# emonTH_V1_4.net
KiCad netlist of a schematic drawn in EAGLE
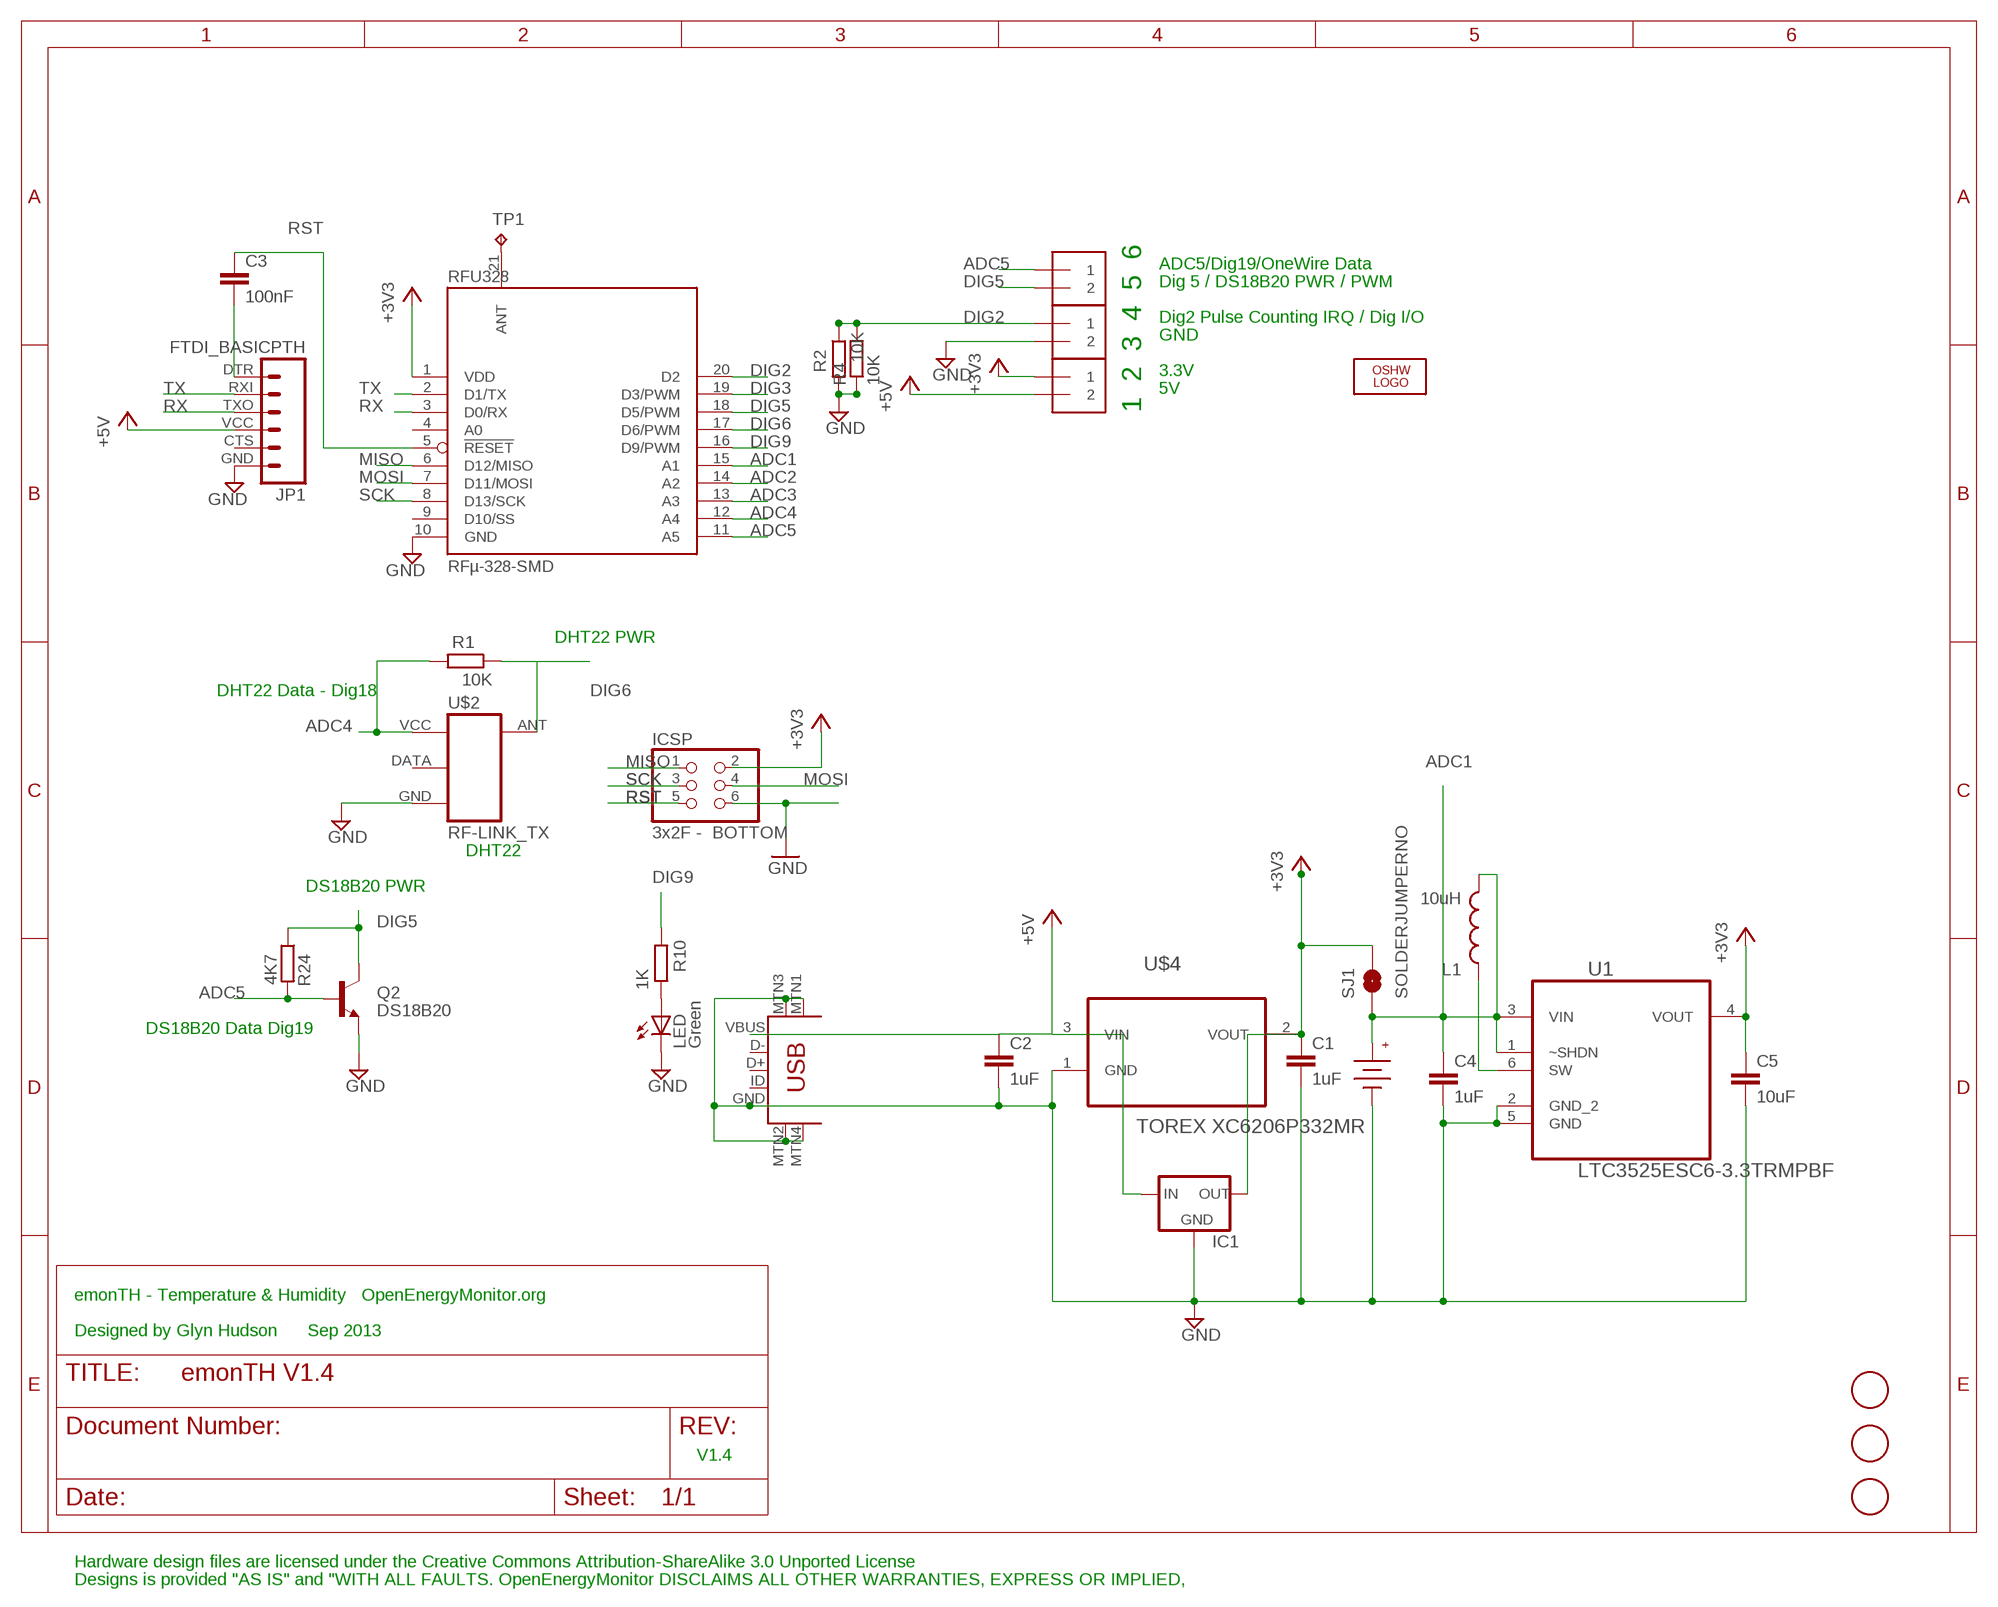
[diagram p0: schematic, sheet 1]

(export (version "E")
  (design (tool "Eeschema 10.0.6"))
  (components
    (comp (ref "C1")
      (value "1uF")
      (footprint "eagle-import:C0603")
      (libsource (lib "eagle-import") (part "C-EUC0603"))
    )
    (comp (ref "C2")
      (value "1uF")
      (footprint "eagle-import:C0603")
      (libsource (lib "eagle-import") (part "C-EUC0603"))
    )
    (comp (ref "C3")
      (value "100nF")
      (footprint "eagle-import:C0603")
      (libsource (lib "eagle-import") (part "C-EUC0603"))
    )
    (comp (ref "C4")
      (value "1uF")
      (footprint "eagle-import:C0603")
      (libsource (lib "eagle-import") (part "C-EUC0603"))
    )
    (comp (ref "C5")
      (value "10uF")
      (footprint "eagle-import:C0603")
      (libsource (lib "eagle-import") (part "C-EUC0603"))
    )
    (comp (ref "IC1")
      (value "78XXS")
      (footprint "eagle-import:78XXS")
      (libsource (lib "eagle-import") (part "78XXS"))
    )
    (comp (ref "ICSP")
      (value "3x2F - BOTTOM")
      (footprint "eagle-import:2X03")
      (libsource (lib "eagle-import") (part "PINHD-2X3"))
    )
    (comp (ref "J1")
      (value "1X2-3.5MM")
      (footprint "eagle-import:1X2-3.5MM")
      (libsource (lib "eagle-import") (part "1X2-3.5MM"))
    )
    (comp (ref "J2")
      (value "1X2-3.5MM")
      (footprint "eagle-import:1X2-3.5MM")
      (libsource (lib "eagle-import") (part "1X2-3.5MM"))
    )
    (comp (ref "J3")
      (value "1X2-3.5MM")
      (footprint "eagle-import:1X2-3.5MM")
      (libsource (lib "eagle-import") (part "1X2-3.5MM"))
    )
    (comp (ref "JP1")
      (value "FTDI_BASICPTH")
      (footprint "eagle-import:FTDI_BASIC")
      (libsource (lib "eagle-import") (part "FTDI_BASICPTH"))
    )
    (comp (ref "L1")
      (value "10uH")
      (footprint "eagle-import:1210")
      (libsource (lib "eagle-import") (part "INDUCTOR1210"))
    )
    (comp (ref "LED")
      (value "Green")
      (footprint "eagle-import:CHIP-LED0805")
      (libsource (lib "eagle-import") (part "LEDCHIP-LED0805"))
    )
    (comp (ref "LOGO1")
      (value "OSHW_LOGO_10MILX0200-NT")
      (footprint "eagle-import:OSHW_10X200_NOTEXT")
      (libsource (lib "eagle-import") (part "OSHW_LOGO_10MILX0200-NT"))
    )
    (comp (ref "Q2")
      (value "DS18B20")
      (footprint "eagle-import:TO-92")
      (libsource (lib "eagle-import") (part "TRANSISTOR_NPNTO92"))
    )
    (comp (ref "R1")
      (value "10K")
      (footprint "eagle-import:R0603")
      (libsource (lib "eagle-import") (part "resistor_R-EU_R0603"))
    )
    (comp (ref "R2")
      (value "10K")
      (footprint "eagle-import:R0603")
      (libsource (lib "eagle-import") (part "resistor_R-EU_R0603"))
    )
    (comp (ref "R4")
      (value "10K")
      (footprint "eagle-import:0204_7")
      (libsource (lib "eagle-import") (part "R-EU_0204/7"))
    )
    (comp (ref "R10")
      (value "1K")
      (footprint "eagle-import:R0603")
      (libsource (lib "eagle-import") (part "resistor_R-EU_R0603"))
    )
    (comp (ref "R24")
      (value "4K7")
      (footprint "eagle-import:R0603")
      (libsource (lib "eagle-import") (part "resistor_R-EU_R0603"))
    )
    (comp (ref "RFU328")
      (value "RFµ-328-SMD")
      (footprint "eagle-import:RFµ-328-LANDING")
      (libsource (lib "eagle-import") (part "RFµ-328-SMD"))
    )
    (comp (ref "SJ1")
      (value "SOLDERJUMPERNO")
      (footprint "eagle-import:SJ_2S-NO")
      (libsource (lib "eagle-import") (part "SOLDERJUMPERNO"))
    )
    (comp (ref "TP1")
      (value "TPPAD1-20")
      (footprint "eagle-import:P1-20")
      (libsource (lib "eagle-import") (part "TPPAD1-20"))
    )
    (comp (ref "U$1")
      (value "FIDUCIAL")
      (footprint "eagle-import:FIDUCIAL_1MM")
      (libsource (lib "eagle-import") (part "FIDUCIAL"))
    )
    (comp (ref "U$2")
      (value "RF-LINK_TX")
      (footprint "eagle-import:RF-LINK_TX")
      (libsource (lib "eagle-import") (part "RF-LINK_TX"))
    )
    (comp (ref "U$3")
      (value "3V")
      (footprint "eagle-import:AAA_PCB_HOLDER")
      (libsource (lib "eagle-import") (part "3X_AAA_BATTERY_HOLDER"))
    )
    (comp (ref "U$4")
      (value "TOREX XC6206P332MR")
      (footprint "eagle-import:SOT95P237X112-3N")
      (fields (field (name "MPN") "MCP1700T-3302E/TT"))
      (libsource (lib "eagle-import") (part "MCP1700T-3302E/TT"))
    )
    (comp (ref "U$5")
      (value "USB-MINIB-5PIN")
      (footprint "eagle-import:USB-MINIB-CISECO")
      (libsource (lib "eagle-import") (part "USB-MINIB-5PIN"))
    )
    (comp (ref "U$6")
      (value "FIDUCIAL")
      (footprint "eagle-import:FIDUCIAL_1MM")
      (libsource (lib "eagle-import") (part "FIDUCIAL"))
    )
    (comp (ref "U$7")
      (value "FIDUCIAL")
      (footprint "eagle-import:FIDUCIAL_1MM")
      (libsource (lib "eagle-import") (part "FIDUCIAL"))
    )
    (comp (ref "U1")
      (value "LTC3525ESC6-3.3TRMPBF")
      (footprint "eagle-import:SOT65P210X100-6N")
      (fields (field (name "MPN") "LTC3525ESC6-3.3#TRMPBF"))
      (libsource (lib "eagle-import") (part "LTC3525ESC6-3.3TRMPBF"))
    )
  )
  (nets
    (net (code "1") (name "+3V3") (class "Default")
      (node (ref "C1") (pin "1") (pinfunction "1_1") (pintype "passive"))
      (node (ref "C5") (pin "1") (pinfunction "1_1") (pintype "passive"))
      (node (ref "IC1") (pin "OUT") (pinfunction "OUT_OUT") (pintype "passive"))
      (node (ref "ICSP") (pin "2") (pinfunction "2_2") (pintype "passive"))
      (node (ref "J3") (pin "1") (pinfunction "1_1") (pintype "passive"))
      (node (ref "RFU328") (pin "1") (pinfunction "VDD_1") (pintype "power_in"))
      (node (ref "SJ1") (pin "2") (pinfunction "2_2") (pintype "passive"))
      (node (ref "U$4") (pin "2") (pinfunction "VOUT_2") (pintype "output"))
      (node (ref "U1") (pin "4") (pinfunction "VOUT_4") (pintype "output"))
    )
    (net (code "2") (name "+5V") (class "Default")
      (node (ref "C2") (pin "1") (pinfunction "1_1") (pintype "passive"))
      (node (ref "IC1") (pin "IN") (pinfunction "IN_IN") (pintype "input"))
      (node (ref "J3") (pin "2") (pinfunction "2_2") (pintype "passive"))
      (node (ref "JP1") (pin "VCC") (pinfunction "4_VCC") (pintype "passive"))
      (node (ref "U$4") (pin "3") (pinfunction "VIN_3") (pintype "input"))
      (node (ref "U$5") (pin "VBUS") (pinfunction "VBUS_VBUS") (pintype "bidirectional"))
    )
    (net (code "3") (name "/ADC1") (class "Default")
      (node (ref "C4") (pin "1") (pinfunction "1_1") (pintype "passive"))
      (node (ref "L1") (pin "2") (pinfunction "2_2") (pintype "passive"))
      (node (ref "RFU328") (pin "15") (pinfunction "A1_15") (pintype "bidirectional"))
      (node (ref "SJ1") (pin "1") (pinfunction "1_1") (pintype "passive"))
      (node (ref "U$3") (pin "+") (pinfunction "+_+") (pintype "power_in"))
      (node (ref "U1") (pin "1") (pinfunction "~{SHDN}_1") (pintype "input"))
      (node (ref "U1") (pin "3") (pinfunction "VIN_3") (pintype "input"))
    )
    (net (code "4") (name "/ADC2") (class "Default")
      (node (ref "RFU328") (pin "14") (pinfunction "A2_14") (pintype "bidirectional"))
    )
    (net (code "5") (name "/ADC3") (class "Default")
      (node (ref "RFU328") (pin "13") (pinfunction "A3_13") (pintype "bidirectional"))
    )
    (net (code "6") (name "/ADC4") (class "Default")
      (node (ref "R1") (pin "2") (pinfunction "2_2") (pintype "passive"))
      (node (ref "RFU328") (pin "12") (pinfunction "A4_12") (pintype "output"))
      (node (ref "U$2") (pin "VCC") (pinfunction "+5V_VCC") (pintype "power_in"))
    )
    (net (code "7") (name "/ADC5") (class "Default")
      (node (ref "J1") (pin "1") (pinfunction "1_1") (pintype "passive"))
      (node (ref "Q2") (pin "2") (pinfunction "B_2") (pintype "passive"))
      (node (ref "R24") (pin "2") (pinfunction "2_2") (pintype "passive"))
      (node (ref "RFU328") (pin "11") (pinfunction "A5_11") (pintype "bidirectional"))
    )
    (net (code "8") (name "/DIG2") (class "Default")
      (node (ref "J2") (pin "1") (pinfunction "1_1") (pintype "passive"))
      (node (ref "R2") (pin "1") (pinfunction "1_1") (pintype "passive"))
      (node (ref "R4") (pin "2") (pinfunction "2_2") (pintype "passive"))
      (node (ref "RFU328") (pin "20") (pinfunction "D2_20") (pintype "bidirectional"))
    )
    (net (code "9") (name "/DIG3") (class "Default")
      (node (ref "RFU328") (pin "19") (pinfunction "D3/PWM_19") (pintype "bidirectional"))
    )
    (net (code "10") (name "/DIG5") (class "Default")
      (node (ref "J1") (pin "2") (pinfunction "2_2") (pintype "passive"))
      (node (ref "Q2") (pin "3") (pinfunction "C_3") (pintype "passive"))
      (node (ref "R24") (pin "1") (pinfunction "1_1") (pintype "passive"))
      (node (ref "RFU328") (pin "18") (pinfunction "D5/PWM_18") (pintype "bidirectional"))
    )
    (net (code "11") (name "/DIG6") (class "Default")
      (node (ref "R1") (pin "1") (pinfunction "1_1") (pintype "passive"))
      (node (ref "RFU328") (pin "17") (pinfunction "D6/PWM_17") (pintype "bidirectional"))
      (node (ref "U$2") (pin "ANT") (pinfunction "ANT_ANT") (pintype "passive"))
    )
    (net (code "12") (name "/DIG9") (class "Default")
      (node (ref "R10") (pin "2") (pinfunction "2_2") (pintype "passive"))
      (node (ref "RFU328") (pin "16") (pinfunction "D9/PWM_16") (pintype "input"))
    )
    (net (code "13") (name "/MISO") (class "Default")
      (node (ref "ICSP") (pin "1") (pinfunction "1_1") (pintype "passive"))
      (node (ref "RFU328") (pin "6") (pinfunction "D12/MISO_6") (pintype "bidirectional"))
    )
    (net (code "14") (name "/MOSI") (class "Default")
      (node (ref "ICSP") (pin "4") (pinfunction "4_4") (pintype "passive"))
      (node (ref "RFU328") (pin "7") (pinfunction "D11/MOSI_7") (pintype "bidirectional"))
    )
    (net (code "15") (name "/RST") (class "Default")
      (node (ref "C3") (pin "1") (pinfunction "1_1") (pintype "passive"))
      (node (ref "ICSP") (pin "5") (pinfunction "5_5") (pintype "passive"))
      (node (ref "RFU328") (pin "5") (pinfunction "~{RESET}_5") (pintype "input"))
    )
    (net (code "16") (name "/RX") (class "Default")
      (node (ref "JP1") (pin "TXO") (pinfunction "3_TXO") (pintype "passive"))
      (node (ref "RFU328") (pin "3") (pinfunction "D0/RX_3") (pintype "input"))
    )
    (net (code "17") (name "/SCK") (class "Default")
      (node (ref "ICSP") (pin "3") (pinfunction "3_3") (pintype "passive"))
      (node (ref "RFU328") (pin "8") (pinfunction "D13/SCK_8") (pintype "bidirectional"))
    )
    (net (code "18") (name "/TX") (class "Default")
      (node (ref "JP1") (pin "RXI") (pinfunction "2_RXI") (pintype "passive"))
      (node (ref "RFU328") (pin "2") (pinfunction "D1/TX_2") (pintype "output"))
    )
    (net (code "19") (name "GND") (class "Default")
      (node (ref "C1") (pin "2") (pinfunction "2_2") (pintype "passive"))
      (node (ref "C2") (pin "2") (pinfunction "2_2") (pintype "passive"))
      (node (ref "C4") (pin "2") (pinfunction "2_2") (pintype "passive"))
      (node (ref "C5") (pin "2") (pinfunction "2_2") (pintype "passive"))
      (node (ref "IC1") (pin "GND") (pinfunction "GND_GND") (pintype "input"))
      (node (ref "ICSP") (pin "6") (pinfunction "6_6") (pintype "passive"))
      (node (ref "J2") (pin "2") (pinfunction "2_2") (pintype "passive"))
      (node (ref "JP1") (pin "GND") (pinfunction "6_GND") (pintype "passive"))
      (node (ref "LED") (pin "C") (pinfunction "C_C") (pintype "passive"))
      (node (ref "Q2") (pin "1") (pinfunction "E_1") (pintype "passive"))
      (node (ref "R2") (pin "2") (pinfunction "2_2") (pintype "passive"))
      (node (ref "R4") (pin "1") (pinfunction "1_1") (pintype "passive"))
      (node (ref "RFU328") (pin "10") (pinfunction "GND_10") (pintype "power_in"))
      (node (ref "U$2") (pin "GND") (pinfunction "GND_GND") (pintype "power_in"))
      (node (ref "U$3") (pin "-") (pinfunction "-_-") (pintype "power_in"))
      (node (ref "U$4") (pin "1") (pinfunction "GND_1") (pintype "passive"))
      (node (ref "U$5") (pin "GND") (pinfunction "GND_GND") (pintype "bidirectional"))
      (node (ref "U$5") (pin "MTN1") (pinfunction "MTN2_MTN1") (pintype "bidirectional"))
      (node (ref "U$5") (pin "MTN2") (pinfunction "MTN3_MTN2") (pintype "bidirectional"))
      (node (ref "U$5") (pin "MTN3") (pinfunction "MTN1_MTN3") (pintype "bidirectional"))
      (node (ref "U$5") (pin "MTN4") (pinfunction "MTN4_MTN4") (pintype "bidirectional"))
      (node (ref "U1") (pin "2") (pinfunction "GND_2_2") (pintype "passive"))
      (node (ref "U1") (pin "5") (pinfunction "GND_5") (pintype "passive"))
    )
    (net (code "20") (name "Net-(JP1-1)") (class "Default")
      (node (ref "C3") (pin "2") (pinfunction "2_2") (pintype "passive"))
      (node (ref "JP1") (pin "DTR") (pinfunction "1_DTR") (pintype "passive"))
    )
    (net (code "21") (name "Net-(LED-PadA)") (class "Default")
      (node (ref "LED") (pin "A") (pinfunction "A_A") (pintype "passive"))
      (node (ref "R10") (pin "1") (pinfunction "1_1") (pintype "passive"))
    )
    (net (code "22") (name "Net-(RFU328-ANT)") (class "Default")
      (node (ref "RFU328") (pin "21") (pinfunction "ANT_21") (pintype "output"))
      (node (ref "TP1") (pin "TP") (pinfunction "TP_TP") (pintype "input"))
    )
    (net (code "23") (name "Net-(U1-SW)") (class "Default")
      (node (ref "L1") (pin "1") (pinfunction "1_1") (pintype "passive"))
      (node (ref "U1") (pin "6") (pinfunction "SW_6") (pintype "input"))
    )
    (net (code "24") (name "unconnected-(JP1-5-PadCTS)") (class "Default")
      (node (ref "JP1") (pin "CTS") (pinfunction "5_CTS") (pintype "passive"))
    )
    (net (code "25") (name "unconnected-(RFU328-A0-Pad4)") (class "Default")
      (node (ref "RFU328") (pin "4") (pinfunction "A0_4") (pintype "bidirectional"))
    )
    (net (code "26") (name "unconnected-(RFU328-D10{slash}SS-Pad9)") (class "Default")
      (node (ref "RFU328") (pin "9") (pinfunction "D10/SS_9") (pintype "bidirectional"))
    )
    (net (code "27") (name "unconnected-(U$2-PadDATA)") (class "Default")
      (node (ref "U$2") (pin "DATA") (pinfunction "DATA_DATA") (pintype "input"))
    )
    (net (code "28") (name "unconnected-(U$5-PadD+)") (class "Default")
      (node (ref "U$5") (pin "D+") (pinfunction "D+_D+") (pintype "bidirectional"))
    )
    (net (code "29") (name "unconnected-(U$5-PadD-)") (class "Default")
      (node (ref "U$5") (pin "D-") (pinfunction "D-_D-") (pintype "bidirectional"))
    )
    (net (code "30") (name "unconnected-(U$5-PadID)") (class "Default")
      (node (ref "U$5") (pin "ID") (pinfunction "ID_ID") (pintype "bidirectional"))
    )
  )
)
